# ASD2201.net
KiCad netlist of a schematic drawn in EAGLE
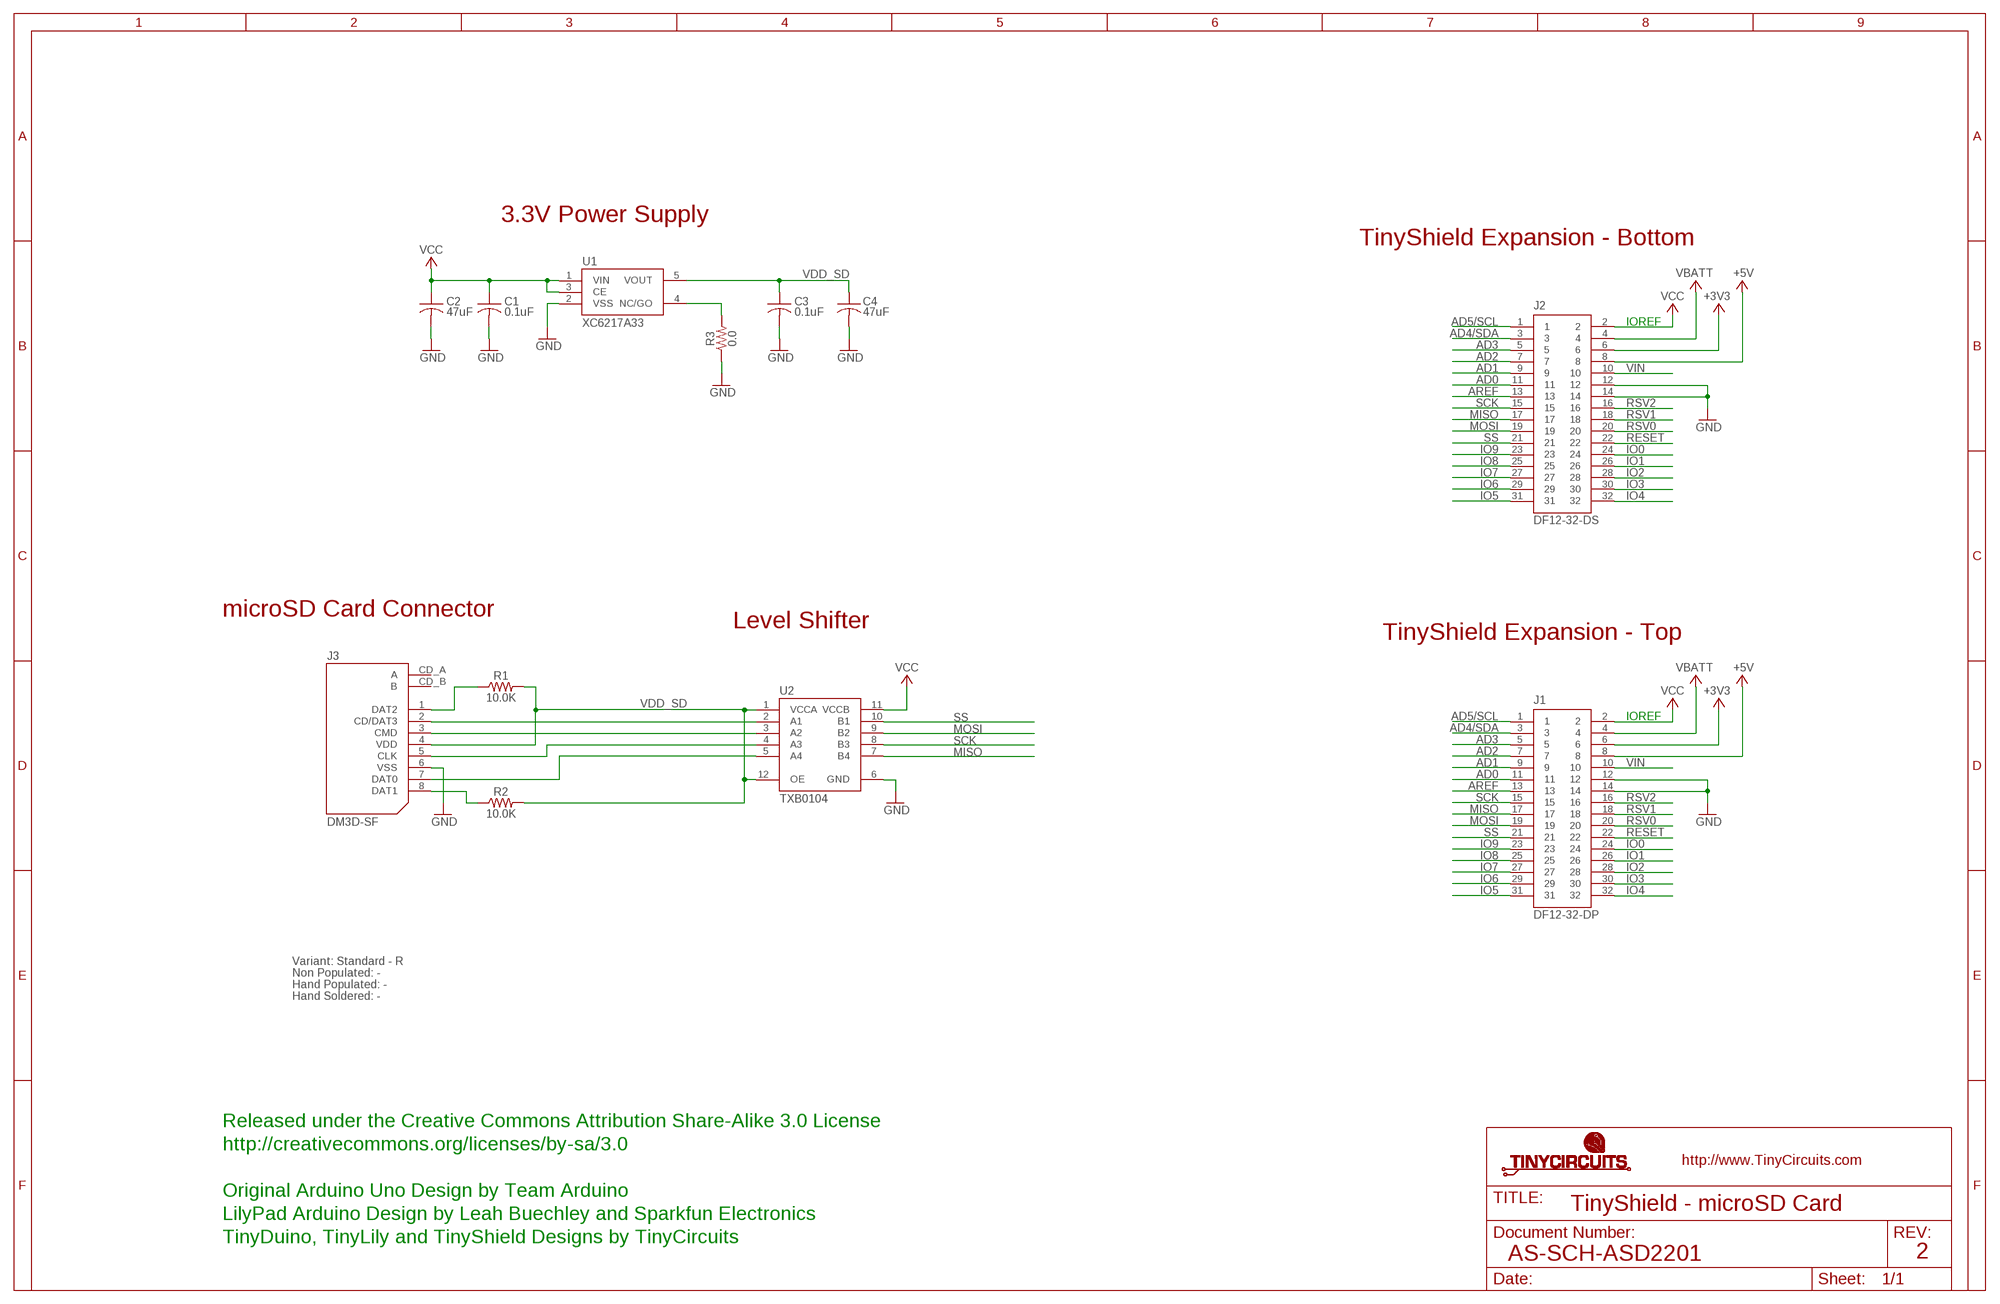
[diagram p0: schematic, sheet 1]

(export (version "E")
  (design (tool "Eeschema 10.0.6"))
  (components
    (comp (ref "C1")
      (value "0.1uF")
      (footprint "eagle-import:C0402")
      (fields (field (name "PARTNO") "AS-ITM-00008") (field (name "PARTNO_1") "AS-ITM-00008"))
      (libsource (lib "eagle-import") (part "AS-ITM-00008"))
    )
    (comp (ref "C2")
      (value "47uF")
      (footprint "eagle-import:C1206")
      (fields (field (name "PARTNO") "AS-ITM-00049"))
      (libsource (lib "eagle-import") (part "AS-ITM-00049"))
    )
    (comp (ref "C3")
      (value "0.1uF")
      (footprint "eagle-import:C0402")
      (fields (field (name "PARTNO") "AS-ITM-00008") (field (name "PARTNO_1") "AS-ITM-00008"))
      (libsource (lib "eagle-import") (part "AS-ITM-00008"))
    )
    (comp (ref "C4")
      (value "47uF")
      (footprint "eagle-import:C1206")
      (fields (field (name "PARTNO") "AS-ITM-00049"))
      (libsource (lib "eagle-import") (part "AS-ITM-00049"))
    )
    (comp (ref "J1")
      (value "DF12-32-DP")
      (footprint "eagle-import:DF12-32-DP")
      (fields (field (name "PARTNO") "AS-ITM-00015") (field (name "PARTNO_1") "AS-ITM-00015"))
      (libsource (lib "eagle-import") (part "AS-ITM-00015"))
    )
    (comp (ref "J2")
      (value "DF12-32-DS")
      (footprint "eagle-import:DF12-32-DS")
      (fields (field (name "PARTNO") "AS-ITM-00012") (field (name "PARTNO_1") "AS-ITM-00012"))
      (libsource (lib "eagle-import") (part "AS-ITM-00012"))
    )
    (comp (ref "J3")
      (value "DM3D-SF")
      (footprint "eagle-import:SD_CARD")
      (fields (field (name "PARTNO") "AS-ITM-00047"))
      (libsource (lib "eagle-import") (part "AS-ITM-00047"))
    )
    (comp (ref "R1")
      (value "10.0K")
      (footprint "eagle-import:0402")
      (fields (field (name "PARTNO") "AS-ITM-00032"))
      (libsource (lib "eagle-import") (part "AS-ITM-00032"))
    )
    (comp (ref "R2")
      (value "10.0K")
      (footprint "eagle-import:0402")
      (fields (field (name "PARTNO") "AS-ITM-00032"))
      (libsource (lib "eagle-import") (part "AS-ITM-00032"))
    )
    (comp (ref "R3")
      (value "0.0")
      (footprint "eagle-import:0402")
      (fields (field (name "PARTNO") "AS-ITM-00076"))
      (libsource (lib "eagle-import") (part "AS-ITM-00076"))
    )
    (comp (ref "U1")
      (value "XC6217A33")
      (footprint "eagle-import:SOT-25")
      (fields (field (name "PARTNO") "AS-ITM-00249") (field (name "PARTNO_1") "AS-ITM-00249"))
      (libsource (lib "eagle-import") (part "AS-ITM-00249"))
    )
    (comp (ref "U2")
      (value "TXB0104")
      (footprint "eagle-import:UQFN-12")
      (fields (field (name "PARTNO") "AS-ITM-00048"))
      (libsource (lib "eagle-import") (part "AS-ITM-00048"))
    )
  )
  (nets
    (net (code "1") (name "+3V3") (class "Default")
      (node (ref "J1") (pin "6") (pinfunction "6_6") (pintype "bidirectional"))
      (node (ref "J2") (pin "6") (pinfunction "6_6") (pintype "bidirectional"))
    )
    (net (code "2") (name "+5V") (class "Default")
      (node (ref "J1") (pin "8") (pinfunction "8_8") (pintype "bidirectional"))
      (node (ref "J2") (pin "8") (pinfunction "8_8") (pintype "bidirectional"))
    )
    (net (code "3") (name "/AD0") (class "Default")
      (node (ref "J1") (pin "11") (pinfunction "11_11") (pintype "bidirectional"))
      (node (ref "J2") (pin "11") (pinfunction "11_11") (pintype "bidirectional"))
    )
    (net (code "4") (name "/AD1") (class "Default")
      (node (ref "J1") (pin "9") (pinfunction "9_9") (pintype "bidirectional"))
      (node (ref "J2") (pin "9") (pinfunction "9_9") (pintype "bidirectional"))
    )
    (net (code "5") (name "/AD2") (class "Default")
      (node (ref "J1") (pin "7") (pinfunction "7_7") (pintype "bidirectional"))
      (node (ref "J2") (pin "7") (pinfunction "7_7") (pintype "bidirectional"))
    )
    (net (code "6") (name "/AD3") (class "Default")
      (node (ref "J1") (pin "5") (pinfunction "5_5") (pintype "bidirectional"))
      (node (ref "J2") (pin "5") (pinfunction "5_5") (pintype "bidirectional"))
    )
    (net (code "7") (name "/AD4{slash}SDA") (class "Default")
      (node (ref "J1") (pin "3") (pinfunction "3_3") (pintype "bidirectional"))
      (node (ref "J2") (pin "3") (pinfunction "3_3") (pintype "bidirectional"))
    )
    (net (code "8") (name "/AD5{slash}SCL") (class "Default")
      (node (ref "J1") (pin "1") (pinfunction "1_1") (pintype "bidirectional"))
      (node (ref "J2") (pin "1") (pinfunction "1_1") (pintype "bidirectional"))
    )
    (net (code "9") (name "/AREF") (class "Default")
      (node (ref "J1") (pin "13") (pinfunction "13_13") (pintype "bidirectional"))
      (node (ref "J2") (pin "13") (pinfunction "13_13") (pintype "bidirectional"))
    )
    (net (code "10") (name "/IO0") (class "Default")
      (node (ref "J1") (pin "24") (pinfunction "24_24") (pintype "bidirectional"))
      (node (ref "J2") (pin "24") (pinfunction "24_24") (pintype "bidirectional"))
    )
    (net (code "11") (name "/IO1") (class "Default")
      (node (ref "J1") (pin "26") (pinfunction "26_26") (pintype "bidirectional"))
      (node (ref "J2") (pin "26") (pinfunction "26_26") (pintype "bidirectional"))
    )
    (net (code "12") (name "/IO2") (class "Default")
      (node (ref "J1") (pin "28") (pinfunction "28_28") (pintype "bidirectional"))
      (node (ref "J2") (pin "28") (pinfunction "28_28") (pintype "bidirectional"))
    )
    (net (code "13") (name "/IO3") (class "Default")
      (node (ref "J1") (pin "30") (pinfunction "30_30") (pintype "bidirectional"))
      (node (ref "J2") (pin "30") (pinfunction "30_30") (pintype "bidirectional"))
    )
    (net (code "14") (name "/IO4") (class "Default")
      (node (ref "J1") (pin "32") (pinfunction "32_32") (pintype "bidirectional"))
      (node (ref "J2") (pin "32") (pinfunction "32_32") (pintype "bidirectional"))
    )
    (net (code "15") (name "/IO5") (class "Default")
      (node (ref "J1") (pin "31") (pinfunction "31_31") (pintype "bidirectional"))
      (node (ref "J2") (pin "31") (pinfunction "31_31") (pintype "bidirectional"))
    )
    (net (code "16") (name "/IO6") (class "Default")
      (node (ref "J1") (pin "29") (pinfunction "29_29") (pintype "bidirectional"))
      (node (ref "J2") (pin "29") (pinfunction "29_29") (pintype "bidirectional"))
    )
    (net (code "17") (name "/IO7") (class "Default")
      (node (ref "J1") (pin "27") (pinfunction "27_27") (pintype "bidirectional"))
      (node (ref "J2") (pin "27") (pinfunction "27_27") (pintype "bidirectional"))
    )
    (net (code "18") (name "/IO8") (class "Default")
      (node (ref "J1") (pin "25") (pinfunction "25_25") (pintype "bidirectional"))
      (node (ref "J2") (pin "25") (pinfunction "25_25") (pintype "bidirectional"))
    )
    (net (code "19") (name "/IO9") (class "Default")
      (node (ref "J1") (pin "23") (pinfunction "23_23") (pintype "bidirectional"))
      (node (ref "J2") (pin "23") (pinfunction "23_23") (pintype "bidirectional"))
    )
    (net (code "20") (name "/MISO") (class "Default")
      (node (ref "J1") (pin "17") (pinfunction "17_17") (pintype "bidirectional"))
      (node (ref "J2") (pin "17") (pinfunction "17_17") (pintype "bidirectional"))
      (node (ref "U2") (pin "7") (pinfunction "B4_7") (pintype "bidirectional"))
    )
    (net (code "21") (name "/MOSI") (class "Default")
      (node (ref "J1") (pin "19") (pinfunction "19_19") (pintype "bidirectional"))
      (node (ref "J2") (pin "19") (pinfunction "19_19") (pintype "bidirectional"))
      (node (ref "U2") (pin "9") (pinfunction "B2_9") (pintype "bidirectional"))
    )
    (net (code "22") (name "/RESET") (class "Default")
      (node (ref "J1") (pin "22") (pinfunction "22_22") (pintype "bidirectional"))
      (node (ref "J2") (pin "22") (pinfunction "22_22") (pintype "bidirectional"))
    )
    (net (code "23") (name "/RSV0") (class "Default")
      (node (ref "J1") (pin "20") (pinfunction "20_20") (pintype "bidirectional"))
      (node (ref "J2") (pin "20") (pinfunction "20_20") (pintype "bidirectional"))
    )
    (net (code "24") (name "/RSV1") (class "Default")
      (node (ref "J1") (pin "18") (pinfunction "18_18") (pintype "bidirectional"))
      (node (ref "J2") (pin "18") (pinfunction "18_18") (pintype "bidirectional"))
    )
    (net (code "25") (name "/RSV2") (class "Default")
      (node (ref "J1") (pin "16") (pinfunction "16_16") (pintype "bidirectional"))
      (node (ref "J2") (pin "16") (pinfunction "16_16") (pintype "bidirectional"))
    )
    (net (code "26") (name "/SCK") (class "Default")
      (node (ref "J1") (pin "15") (pinfunction "15_15") (pintype "bidirectional"))
      (node (ref "J2") (pin "15") (pinfunction "15_15") (pintype "bidirectional"))
      (node (ref "U2") (pin "8") (pinfunction "B3_8") (pintype "bidirectional"))
    )
    (net (code "27") (name "/SS") (class "Default")
      (node (ref "J1") (pin "21") (pinfunction "21_21") (pintype "bidirectional"))
      (node (ref "J2") (pin "21") (pinfunction "21_21") (pintype "bidirectional"))
      (node (ref "U2") (pin "10") (pinfunction "B1_10") (pintype "bidirectional"))
    )
    (net (code "28") (name "/VDD_SD") (class "Default")
      (node (ref "C3") (pin "1") (pinfunction "1_1") (pintype "passive"))
      (node (ref "C4") (pin "1") (pinfunction "1_1") (pintype "passive"))
      (node (ref "J3") (pin "4") (pinfunction "VDD_4") (pintype "bidirectional"))
      (node (ref "R1") (pin "2") (pinfunction "2_2") (pintype "passive"))
      (node (ref "R2") (pin "2") (pinfunction "2_2") (pintype "passive"))
      (node (ref "U1") (pin "5") (pinfunction "VOUT_5") (pintype "bidirectional"))
      (node (ref "U2") (pin "1") (pinfunction "VCCA_1") (pintype "bidirectional"))
      (node (ref "U2") (pin "12") (pinfunction "OE_12") (pintype "bidirectional"))
    )
    (net (code "29") (name "/VIN") (class "Default")
      (node (ref "J1") (pin "10") (pinfunction "10_10") (pintype "bidirectional"))
      (node (ref "J2") (pin "10") (pinfunction "10_10") (pintype "bidirectional"))
    )
    (net (code "30") (name "GND") (class "Default")
      (node (ref "C1") (pin "2") (pinfunction "2_2") (pintype "passive"))
      (node (ref "C2") (pin "2") (pinfunction "2_2") (pintype "passive"))
      (node (ref "C3") (pin "2") (pinfunction "2_2") (pintype "passive"))
      (node (ref "C4") (pin "2") (pinfunction "2_2") (pintype "passive"))
      (node (ref "J1") (pin "12") (pinfunction "12_12") (pintype "bidirectional"))
      (node (ref "J1") (pin "14") (pinfunction "14_14") (pintype "bidirectional"))
      (node (ref "J2") (pin "12") (pinfunction "12_12") (pintype "bidirectional"))
      (node (ref "J2") (pin "14") (pinfunction "14_14") (pintype "bidirectional"))
      (node (ref "J3") (pin "6") (pinfunction "VSS_6") (pintype "bidirectional"))
      (node (ref "R3") (pin "1") (pinfunction "1_1") (pintype "passive"))
      (node (ref "U1") (pin "2") (pinfunction "VSS_2") (pintype "power_in"))
      (node (ref "U2") (pin "6") (pinfunction "GND_6") (pintype "bidirectional"))
    )
    (net (code "31") (name "Net-(J3-CD{slash}DAT3)") (class "Default")
      (node (ref "J3") (pin "2") (pinfunction "CD/DAT3_2") (pintype "bidirectional"))
      (node (ref "U2") (pin "2") (pinfunction "A1_2") (pintype "bidirectional"))
    )
    (net (code "32") (name "Net-(J3-CLK)") (class "Default")
      (node (ref "J3") (pin "5") (pinfunction "CLK_5") (pintype "bidirectional"))
      (node (ref "U2") (pin "4") (pinfunction "A3_4") (pintype "bidirectional"))
    )
    (net (code "33") (name "Net-(J3-CMD)") (class "Default")
      (node (ref "J3") (pin "3") (pinfunction "CMD_3") (pintype "bidirectional"))
      (node (ref "U2") (pin "3") (pinfunction "A2_3") (pintype "bidirectional"))
    )
    (net (code "34") (name "Net-(J3-DAT0)") (class "Default")
      (node (ref "J3") (pin "7") (pinfunction "DAT0_7") (pintype "bidirectional"))
      (node (ref "U2") (pin "5") (pinfunction "A4_5") (pintype "bidirectional"))
    )
    (net (code "35") (name "Net-(J3-DAT1)") (class "Default")
      (node (ref "J3") (pin "8") (pinfunction "DAT1_8") (pintype "bidirectional"))
      (node (ref "R2") (pin "1") (pinfunction "1_1") (pintype "passive"))
    )
    (net (code "36") (name "Net-(J3-DAT2)") (class "Default")
      (node (ref "J3") (pin "1") (pinfunction "DAT2_1") (pintype "bidirectional"))
      (node (ref "R1") (pin "1") (pinfunction "1_1") (pintype "passive"))
    )
    (net (code "37") (name "Net-(U1-NC{slash}GO)") (class "Default")
      (node (ref "R3") (pin "2") (pinfunction "2_2") (pintype "passive"))
      (node (ref "U1") (pin "4") (pinfunction "NC/GO_4") (pintype "bidirectional"))
    )
    (net (code "38") (name "VBATT") (class "Default")
      (node (ref "J1") (pin "4") (pinfunction "4_4") (pintype "bidirectional"))
      (node (ref "J2") (pin "4") (pinfunction "4_4") (pintype "bidirectional"))
    )
    (net (code "39") (name "VCC") (class "Default")
      (node (ref "C1") (pin "1") (pinfunction "1_1") (pintype "passive"))
      (node (ref "C2") (pin "1") (pinfunction "1_1") (pintype "passive"))
      (node (ref "J1") (pin "2") (pinfunction "2_2") (pintype "bidirectional"))
      (node (ref "J2") (pin "2") (pinfunction "2_2") (pintype "bidirectional"))
      (node (ref "U1") (pin "1") (pinfunction "VIN_1") (pintype "bidirectional"))
      (node (ref "U1") (pin "3") (pinfunction "CE_3") (pintype "bidirectional"))
      (node (ref "U2") (pin "11") (pinfunction "VCCB_11") (pintype "bidirectional"))
    )
    (net (code "40") (name "unconnected-(J3-A-PadCD_A)") (class "Default")
      (node (ref "J3") (pin "CD_A") (pinfunction "A_CD_A") (pintype "bidirectional"))
    )
    (net (code "41") (name "unconnected-(J3-B-PadCD_B)") (class "Default")
      (node (ref "J3") (pin "CD_B") (pinfunction "B_CD_B") (pintype "bidirectional"))
    )
  )
)
